# fuelPumpSchematic.net
KiCad netlist of a schematic drawn in Altium Designer
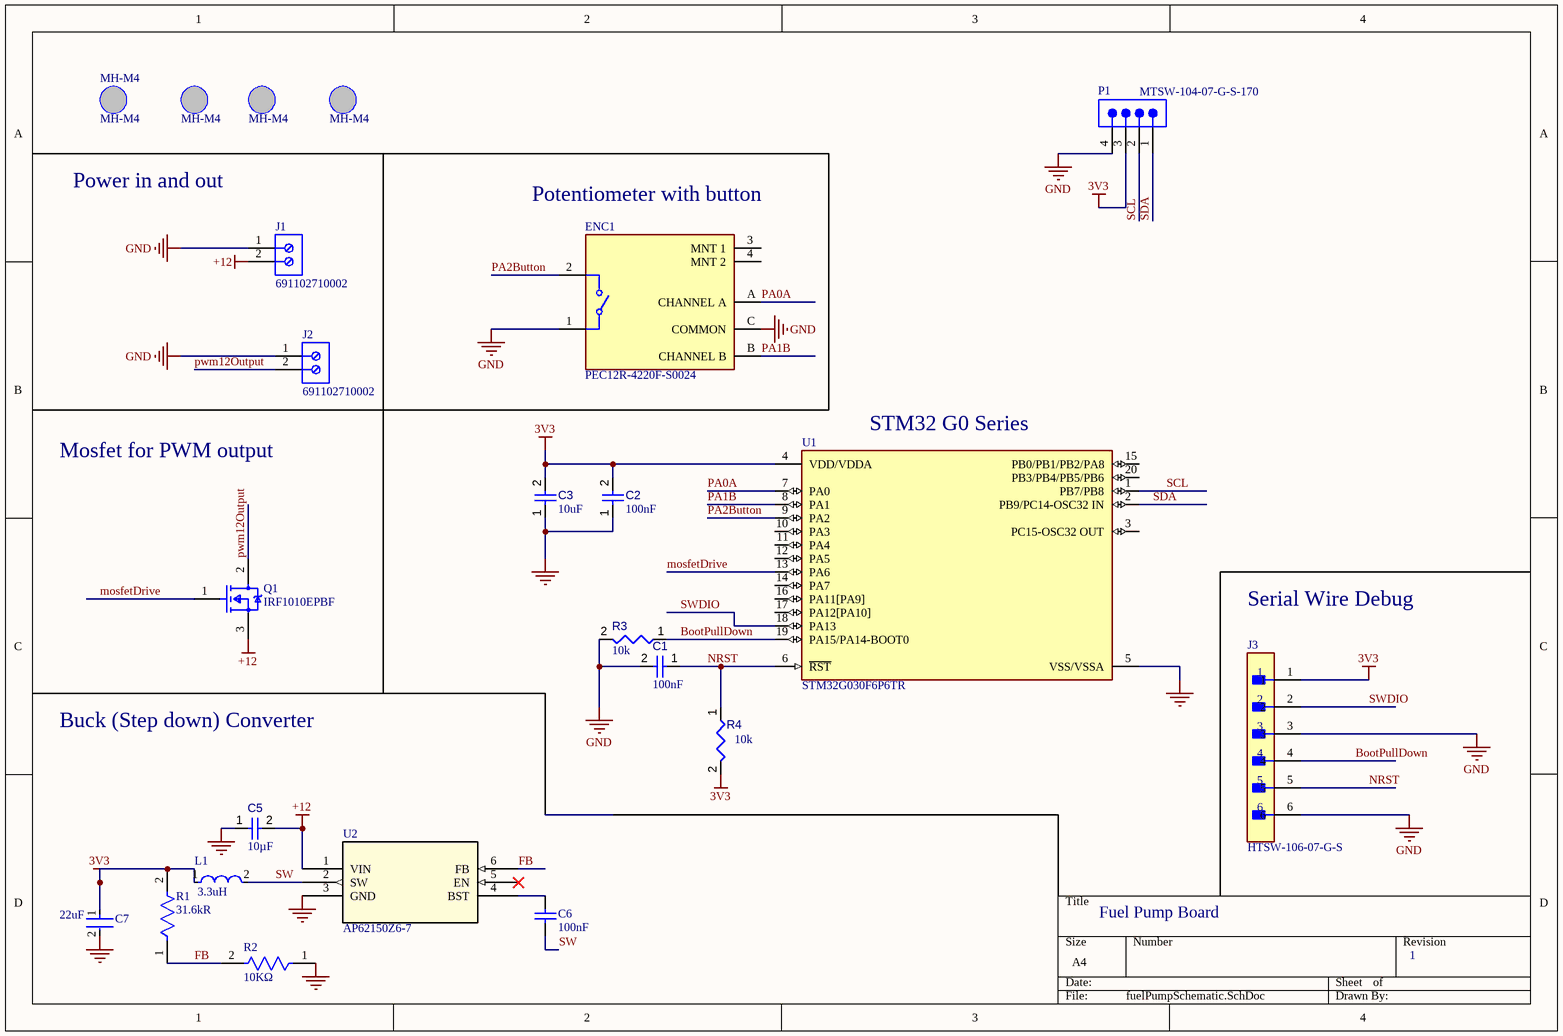
[diagram p0: fuelPumpSchematic.SchDoc]

(export (version "E")
  (design (tool "Eeschema 10.0.6"))
  (components
    (comp (ref "C1")
      (value "100nF")
      (footprint "CAPC2013X95X50LL10T25")
      (description "Chip Capacitor, 100 nF, +/- 10%, 50 V, 0805 (2012 Metric)")
      (fields (field (name "TOLERANCE") "10%") (field (name "Comment") "Capacitor 100 nF +/-10% 50 V 0805"))
      (libsource (lib "Sami Ghozlani") (part "CAP-NP-2"))
    )
    (comp (ref "C2")
      (value "100nF")
      (footprint "CAPC2013X95X50LL10T25")
      (description "Chip Capacitor, 100 nF, +/- 10%, 50 V, 0805 (2012 Metric)")
      (fields (field (name "TOLERANCE") "10%") (field (name "Comment") "Capacitor 100 nF +/-10% 50 V 0805"))
      (libsource (lib "Sami Ghozlani") (part "CAP-NP-2"))
    )
    (comp (ref "C3")
      (value "10uF")
      (footprint "CAPC2013X95X50LL10T25")
      (description "Chip Capacitor, 100 nF, +/- 10%, 50 V, 0805 (2012 Metric)")
      (fields (field (name "TOLERANCE") "10%") (field (name "Comment") "Capacitor 100 nF +/-10% 50 V 0805"))
      (libsource (lib "Sami Ghozlani") (part "CAP-NP-2"))
    )
    (comp (ref "C5")
      (value "10µF")
      (footprint "CAPC0603(1608)100_L")
      (description "Chip Capacitor, 10µF +/-20%, 10V, 0603, Thickness 1 mm")
      (fields (field (name "TOLERANCE") "10%") (field (name "Comment") "Capacitor 10µF +/-20% 10V 0603"))
      (libsource (lib "Sami Ghozlani") (part "CAP-NP-2"))
    )
    (comp (ref "C6")
      (value "VJ0603Y104KXXAP")
      (footprint "CAPC1608X92X38NL15T08")
      (fields (field (name "MANUFACTURER") "Vitramon") (field (name "CAPACITANCE") "100nF"))
      (libsource (lib "Altium Content Vault") (part "CAP"))
    )
    (comp (ref "C7")
      (value "GRM186R60J226ME15D")
      (footprint "FP-GRM186-0_2-IPC_B")
      (description "Chip Multilayer Ceramic Capacitors for General Purpose, 0603, 22uF, X5R, 15%, 20%, 6.3V")
      (fields (field (name "TOLERANCE") "20%") (field (name "CAPACITANCE") "22uF"))
      (libsource (lib "Altium Content Vault") (part "02cd4be3c70576c341d710602a673aa"))
    )
    (comp (ref "ENC1")
      (value "PEC12R-4220F-S0024")
      (footprint "FP-PEC12R-4220F-S0024-MFG")
      (description "ROTARY ENCODER MECHANICAL 24PPR")
      (libsource (lib "Altium Content Vault") (part "94c173c7df275f4241826ab5d869309"))
    )
    (comp (ref "J1")
      (value "691102710002")
      (footprint "691102710002")
      (description "102 Series 5MM Pitch Straight, Pcb Terminal Block, Through Hole, 2 Way")
      (fields (field (name "VOLTAGE") "300V"))
      (libsource (lib "Altium Content Vault") (part "TBL - 1R - 02P - Screw"))
    )
    (comp (ref "J2")
      (value "691102710002")
      (footprint "691102710002")
      (description "102 Series 5MM Pitch Straight, Pcb Terminal Block, Through Hole, 2 Way")
      (fields (field (name "VOLTAGE") "300V"))
      (libsource (lib "Altium Content Vault") (part "TBL - 1R - 02P - Screw"))
    )
    (comp (ref "J3")
      (value "HTSW-106-07-G-S")
      (footprint "FP-HTSW-106-07-G-S-MFG")
      (description "CONN HEADER VERT 6POS 2.54MM")
      (libsource (lib "Altium Content Vault") (part "f2cb566baf1c37ab5a3b8e90bbeafd6"))
    )
    (comp (ref "L1")
      (value "3.3uH")
      (footprint "FP-DFE322520F_D-MFG")
      (description "FIXED IND 3.3UH 4200MA INFOTNMNT")
      (libsource (lib "Altium Content Vault") (part "725321dda6339637d4d059423bc1c3c"))
    )
    (comp (ref "MH-M4")
      (value "MH-M4")
      (footprint "MH-M4")
      (description "4.1mm not plated hole")
      (fields (field (name "SOURCE") "SamiSchLib.SchLib"))
      (libsource (lib "Sami Ghozlani") (part "MH-M4"))
    )
    (comp (ref "MH-M5")
      (value "MH-M4")
      (footprint "MH-M4")
      (description "4.1mm not plated hole")
      (fields (field (name "SOURCE") "SamiSchLib.SchLib"))
      (libsource (lib "Sami Ghozlani") (part "MH-M4"))
    )
    (comp (ref "MH-M6")
      (value "MH-M4")
      (footprint "MH-M4")
      (description "4.1mm not plated hole")
      (fields (field (name "SOURCE") "SamiSchLib.SchLib"))
      (libsource (lib "Sami Ghozlani") (part "MH-M4"))
    )
    (comp (ref "MH-M7")
      (value "MH-M4")
      (footprint "MH-M4")
      (description "4.1mm not plated hole")
      (fields (field (name "SOURCE") "SamiSchLib.SchLib"))
      (libsource (lib "Sami Ghozlani") (part "MH-M4"))
    )
    (comp (ref "P1")
      (value "MTSW-104-07-G-S-170")
      (footprint "SMTC-MTSW-104-07-X-S-170")
      (fields (field (name "MANUFACTURER") "Samtec"))
      (libsource (lib "Altium Content Vault") (part "SMTC-MTSW-104-07-X-S-170"))
    )
    (comp (ref "Q1")
      (value "IRF1010EPBF")
      (footprint "FP-PG-TO220-3-MFG")
      (description "MOSFET N-CH 60V 84A TO-220AB")
      (libsource (lib "Altium Content Vault") (part "b09f7f152735e370c1ea22a33fa83d6"))
    )
    (comp (ref "R1")
      (value "AC0603FR-0731K6L")
      (footprint "FP-AC0603-MFG")
      (description "RES 31.6KΩ 1.00% 0.1W 0603")
      (fields (field (name "TOLERANCE") "1%") (field (name "RESISTANCE") "31.6kR"))
      (libsource (lib "Altium Content Vault") (part "1029c3af85768c4190bb7ad29bc67b5"))
    )
    (comp (ref "R2")
      (value "RT0603BRC0710KL")
      (footprint "FP-RT0603-MFG")
      (description "RES SMD 10K OHM 0.1% 1/10W 0603")
      (fields
        (field (name "MANUFACTURER") "Yageo")
        (field (name "TOLERANCE") "0.001")
        (field (name "RESISTANCE") "10KΩ")
      )
      (libsource (lib "Altium Content Vault") (part "1029c3af85768c4190bb7ad29bc67b5"))
    )
    (comp (ref "R3")
      (value "10k")
      (footprint "RESC2013X50X35ML15T15")
      (description "Chip Resistor, 10 KOhm, +/- 1%, 125 mW, -55 to 155 degC, 0805 (2012 Metric)")
      (fields (field (name "TOLERANCE") "1%") (field (name "POWER") "125mW"))
      (libsource (lib "Sami Ghozlani") (part "RES-2"))
    )
    (comp (ref "R4")
      (value "10k")
      (footprint "RESC2013X50X35ML15T15")
      (description "Chip Resistor, 10 KOhm, +/- 1%, 125 mW, -55 to 155 degC, 0805 (2012 Metric)")
      (fields (field (name "TOLERANCE") "1%") (field (name "POWER") "125mW"))
      (libsource (lib "Sami Ghozlani") (part "RES-2"))
    )
    (comp (ref "U1")
      (value "STM32G030F6P6TR")
      (footprint "FP-TSSOP20-YA-IPC_A")
      (description "IC MCU 32BIT 32KB FLASH 20TSSOP")
      (libsource (lib "Altium Content Vault") (part "be9f3bd3d72e89be6370f9e56c175d8"))
    )
    (comp (ref "U2")
      (value "AP62150Z6-7")
      (footprint "SOT563_DIO")
      (description "Description")
      (fields (field (name "COPYRIGHT") "Copyright (C) 2025 Ultra Librarian. All rights reserved."))
      (libsource (lib "Electromechanical - Copie") (part "AP62150Z6-7"))
    )
  )
  (nets
    (net (code "1") (name "+12") (class "Default")
      (node (ref "C5") (pin "2") (pinfunction "2_2") (pintype "passive"))
      (node (ref "J1") (pin "2") (pinfunction "2_2") (pintype "passive"))
      (node (ref "Q1") (pin "3") (pinfunction "S_3") (pintype "passive"))
      (node (ref "U2") (pin "1") (pinfunction "VIN_1") (pintype "power_in"))
    )
    (net (code "2") (name "/BootPullDown") (class "Default")
      (node (ref "J3") (pin "4") (pinfunction "4_4") (pintype "passive"))
      (node (ref "R3") (pin "1") (pinfunction "1_1") (pintype "passive"))
      (node (ref "U1") (pin "19") (pinfunction "PA15/PA14-BOOT0_19") (pintype "bidirectional"))
    )
    (net (code "3") (name "/FB") (class "Default")
      (node (ref "R1") (pin "1") (pinfunction "1_1") (pintype "passive"))
      (node (ref "R2") (pin "2") (pinfunction "2_2") (pintype "passive"))
      (node (ref "U2") (pin "6") (pinfunction "FB_6") (pintype "input"))
    )
    (net (code "4") (name "/NRST") (class "Default")
      (node (ref "C1") (pin "1") (pinfunction "1_1") (pintype "passive"))
      (node (ref "J3") (pin "5") (pinfunction "5_5") (pintype "passive"))
      (node (ref "R4") (pin "1") (pinfunction "1_1") (pintype "passive"))
      (node (ref "U1") (pin "6") (pinfunction "~{RST}_6") (pintype "input"))
    )
    (net (code "5") (name "/PA0A") (class "Default")
      (node (ref "ENC1") (pin "A") (pinfunction "CHANNEL_A_A") (pintype "passive"))
      (node (ref "U1") (pin "7") (pinfunction "PA0_7") (pintype "bidirectional"))
    )
    (net (code "6") (name "/PA1B") (class "Default")
      (node (ref "ENC1") (pin "B") (pinfunction "CHANNEL_B_B") (pintype "passive"))
      (node (ref "U1") (pin "8") (pinfunction "PA1_8") (pintype "bidirectional"))
    )
    (net (code "7") (name "/PA2Button") (class "Default")
      (node (ref "ENC1") (pin "2") (pinfunction "2_2") (pintype "passive"))
      (node (ref "U1") (pin "9") (pinfunction "PA2_9") (pintype "bidirectional"))
    )
    (net (code "8") (name "/SCL") (class "Default")
      (node (ref "P1") (pin "2") (pinfunction "2_2") (pintype "passive"))
      (node (ref "U1") (pin "1") (pinfunction "PB7/PB8_1") (pintype "bidirectional"))
    )
    (net (code "9") (name "/SDA") (class "Default")
      (node (ref "P1") (pin "1") (pinfunction "1_1") (pintype "passive"))
      (node (ref "U1") (pin "2") (pinfunction "PB9/PC14-OSC32_IN_2") (pintype "bidirectional"))
    )
    (net (code "10") (name "/SW") (class "Default")
      (node (ref "C6") (pin "1") (pinfunction "1_1") (pintype "passive"))
      (node (ref "L1") (pin "2") (pinfunction "2_2") (pintype "passive"))
      (node (ref "U2") (pin "2") (pinfunction "SW_2") (pintype "output"))
    )
    (net (code "11") (name "/SWDIO") (class "Default")
      (node (ref "J3") (pin "2") (pinfunction "2_2") (pintype "passive"))
      (node (ref "U1") (pin "18") (pinfunction "PA13_18") (pintype "bidirectional"))
    )
    (net (code "12") (name "/mosfetDrive") (class "Default")
      (node (ref "Q1") (pin "1") (pinfunction "G_1") (pintype "passive"))
      (node (ref "U1") (pin "13") (pinfunction "PA6_13") (pintype "bidirectional"))
    )
    (net (code "13") (name "/pwm12Output") (class "Default")
      (node (ref "J2") (pin "2") (pinfunction "2_2") (pintype "passive"))
      (node (ref "Q1") (pin "2") (pinfunction "D_2") (pintype "passive"))
    )
    (net (code "14") (name "3V3") (class "Default")
      (node (ref "C2") (pin "2") (pinfunction "2_2") (pintype "passive"))
      (node (ref "C3") (pin "2") (pinfunction "2_2") (pintype "passive"))
      (node (ref "C7") (pin "1") (pinfunction "1_1") (pintype "passive"))
      (node (ref "J3") (pin "1") (pinfunction "1_1") (pintype "passive"))
      (node (ref "L1") (pin "1") (pinfunction "1_1") (pintype "passive"))
      (node (ref "P1") (pin "3") (pinfunction "3_3") (pintype "passive"))
      (node (ref "R1") (pin "2") (pinfunction "2_2") (pintype "passive"))
      (node (ref "R4") (pin "2") (pinfunction "2_2") (pintype "passive"))
      (node (ref "U1") (pin "4") (pinfunction "VDD/VDDA_4") (pintype "power_in"))
    )
    (net (code "15") (name "GND") (class "Default")
      (node (ref "C1") (pin "2") (pinfunction "2_2") (pintype "passive"))
      (node (ref "C2") (pin "1") (pinfunction "1_1") (pintype "passive"))
      (node (ref "C3") (pin "1") (pinfunction "1_1") (pintype "passive"))
      (node (ref "C5") (pin "1") (pinfunction "1_1") (pintype "passive"))
      (node (ref "C7") (pin "2") (pinfunction "2_2") (pintype "passive"))
      (node (ref "ENC1") (pin "1") (pinfunction "1_1") (pintype "passive"))
      (node (ref "ENC1") (pin "C") (pinfunction "COMMON_C") (pintype "passive"))
      (node (ref "J1") (pin "1") (pinfunction "1_1") (pintype "passive"))
      (node (ref "J2") (pin "1") (pinfunction "1_1") (pintype "passive"))
      (node (ref "J3") (pin "3") (pinfunction "3_3") (pintype "passive"))
      (node (ref "J3") (pin "6") (pinfunction "6_6") (pintype "passive"))
      (node (ref "P1") (pin "4") (pinfunction "4_4") (pintype "passive"))
      (node (ref "R2") (pin "1") (pinfunction "1_1") (pintype "passive"))
      (node (ref "R3") (pin "2") (pinfunction "2_2") (pintype "passive"))
      (node (ref "U1") (pin "5") (pinfunction "VSS/VSSA_5") (pintype "power_in"))
      (node (ref "U2") (pin "3") (pinfunction "GND_3") (pintype "power_in"))
    )
    (net (code "16") (name "Net-(U2-BST)") (class "Default")
      (node (ref "C6") (pin "2") (pinfunction "2_2") (pintype "passive"))
      (node (ref "U2") (pin "4") (pinfunction "BST_4") (pintype "power_in"))
    )
    (net (code "17") (name "unconnected-(ENC1-MNT_1-Pad3)") (class "Default")
      (node (ref "ENC1") (pin "3") (pinfunction "MNT_1_3") (pintype "passive"))
    )
    (net (code "18") (name "unconnected-(ENC1-MNT_2-Pad4)") (class "Default")
      (node (ref "ENC1") (pin "4") (pinfunction "MNT_2_4") (pintype "passive"))
    )
    (net (code "19") (name "unconnected-(U1-PA3-Pad10)") (class "Default")
      (node (ref "U1") (pin "10") (pinfunction "PA3_10") (pintype "bidirectional"))
    )
    (net (code "20") (name "unconnected-(U1-PA4-Pad11)") (class "Default")
      (node (ref "U1") (pin "11") (pinfunction "PA4_11") (pintype "bidirectional"))
    )
    (net (code "21") (name "unconnected-(U1-PA5-Pad12)") (class "Default")
      (node (ref "U1") (pin "12") (pinfunction "PA5_12") (pintype "bidirectional"))
    )
    (net (code "22") (name "unconnected-(U1-PA7-Pad14)") (class "Default")
      (node (ref "U1") (pin "14") (pinfunction "PA7_14") (pintype "bidirectional"))
    )
    (net (code "23") (name "unconnected-(U1-PA11[PA9]-Pad16)") (class "Default")
      (node (ref "U1") (pin "16") (pinfunction "PA11[PA9]_16") (pintype "bidirectional"))
    )
    (net (code "24") (name "unconnected-(U1-PA12[PA10]-Pad17)") (class "Default")
      (node (ref "U1") (pin "17") (pinfunction "PA12[PA10]_17") (pintype "bidirectional"))
    )
    (net (code "25") (name "unconnected-(U1-PB0{slash}PB1{slash}PB2{slash}PA8-Pad15)") (class "Default")
      (node (ref "U1") (pin "15") (pinfunction "PB0/PB1/PB2/PA8_15") (pintype "bidirectional"))
    )
    (net (code "26") (name "unconnected-(U1-PB3{slash}PB4{slash}PB5{slash}PB6-Pad20)") (class "Default")
      (node (ref "U1") (pin "20") (pinfunction "PB3/PB4/PB5/PB6_20") (pintype "bidirectional"))
    )
    (net (code "27") (name "unconnected-(U1-PC15-OSC32_OUT-Pad3)") (class "Default")
      (node (ref "U1") (pin "3") (pinfunction "PC15-OSC32_OUT_3") (pintype "bidirectional"))
    )
    (net (code "28") (name "unconnected-(U2-EN-Pad5)") (class "Default")
      (node (ref "U2") (pin "5") (pinfunction "EN_5") (pintype "input+no_connect"))
    )
  )
)
